# LM2587_12v.net
KiCad netlist of a schematic drawn in Altium Designer
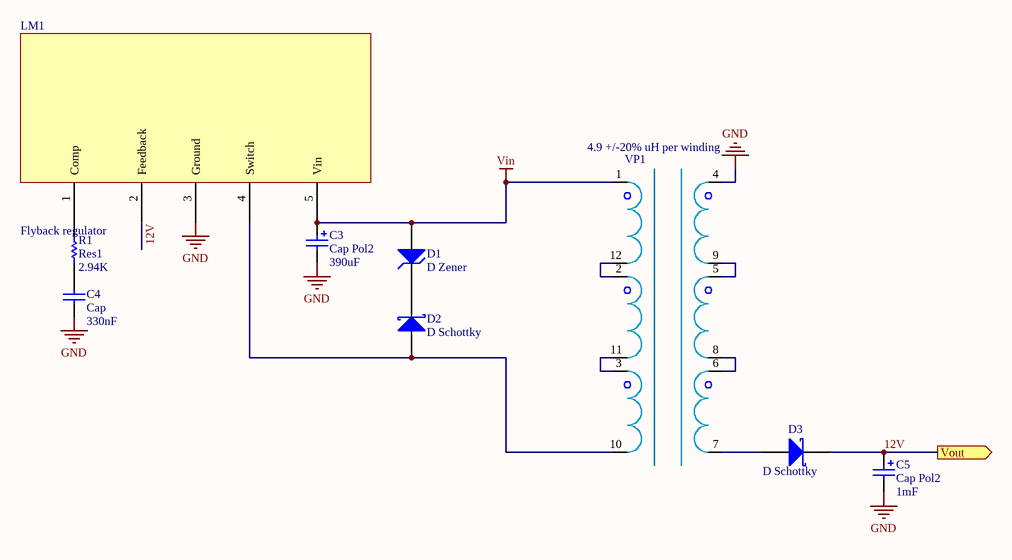
[diagram p0: LM2587_12v.SchDoc]

(export (version "E")
  (design (tool "Eeschema 10.0.6"))
  (components
    (comp (ref "C3")
      (value "Cap Pol2")
      (footprint "AXIAL-0.3")
      (description "Polarized Capacitor (Axial)")
      (fields (field (name "ALTIUM_VALUE") "390uF") (field (name "PUBLISHER") "Altium Limited"))
      (libsource (lib "Miscellaneous Devices") (part "Cap Pol2"))
    )
    (comp (ref "C4")
      (value "Cap")
      (footprint "AXIAL-0.3")
      (description "Capacitor")
      (fields (field (name "ALTIUM_VALUE") "330nF") (field (name "PUBLISHER") "Altium Limited"))
      (libsource (lib "Miscellaneous Devices") (part "Cap"))
    )
    (comp (ref "C5")
      (value "Cap Pol2")
      (footprint "AXIAL-0.3")
      (description "Polarized Capacitor (Axial)")
      (fields (field (name "ALTIUM_VALUE") "1mF") (field (name "PUBLISHER") "Altium Limited"))
      (libsource (lib "Miscellaneous Devices") (part "Cap Pol2"))
    )
    (comp (ref "D1")
      (value "D Zener")
      (footprint "DIODE")
      (description "Zener Diode")
      (fields (field (name "PUBLISHER") "Altium Limited"))
      (libsource (lib "Miscellaneous Devices") (part "D Zener"))
    )
    (comp (ref "D2")
      (value "D Schottky")
      (footprint "DIODE")
      (description "Schottky Diode")
      (fields (field (name "PUBLISHER") "Altium Limited"))
      (libsource (lib "Miscellaneous Devices") (part "D Schottky"))
    )
    (comp (ref "D3")
      (value "D Schottky")
      (footprint "DIODE")
      (description "Schottky Diode")
      (fields (field (name "PUBLISHER") "Altium Limited"))
      (libsource (lib "Miscellaneous Devices") (part "D Schottky"))
    )
    (comp (ref "LM1")
      (value "Flyback regulator")
      (footprint "TS5B")
      (libsource (lib "investigator_regulator") (part "LM2587"))
    )
    (comp (ref "R1")
      (value "Res1")
      (footprint "AXIAL-0.3")
      (description "Resistor")
      (fields (field (name "ALTIUM_VALUE") "2.94K") (field (name "PUBLISHER") "Altium Limited"))
      (libsource (lib "Miscellaneous Devices") (part "Res1"))
    )
    (comp (ref "VP1")
      (value "4.9 +/-20% uH per winding")
      (footprint "TRANSFORMER_SOP12")
      (libsource (lib "investigator_regulator") (part "VP4-0060-R"))
    )
  )
  (nets
    (net (code "1") (name "/12V") (class "Default")
      (node (ref "C5") (pin "1") (pinfunction "1_1") (pintype "passive"))
      (node (ref "D3") (pin "2") (pinfunction "K_2") (pintype "passive"))
      (node (ref "LM1") (pin "2") (pinfunction "Feedback_2") (pintype "passive"))
    )
    (net (code "2") (name "GND") (class "Default")
      (node (ref "C3") (pin "2") (pinfunction "2_2") (pintype "passive"))
      (node (ref "C4") (pin "1") (pinfunction "1_1") (pintype "passive"))
      (node (ref "C5") (pin "2") (pinfunction "2_2") (pintype "passive"))
      (node (ref "LM1") (pin "3") (pinfunction "Ground_3") (pintype "passive"))
      (node (ref "VP1") (pin "4") (pinfunction "4_4") (pintype "passive"))
    )
    (net (code "3") (name "Net-(C4-Pad2)") (class "Default")
      (node (ref "C4") (pin "2") (pinfunction "2_2") (pintype "passive"))
      (node (ref "R1") (pin "1") (pinfunction "1_1") (pintype "passive"))
    )
    (net (code "4") (name "Net-(D1-K)") (class "Default")
      (node (ref "D1") (pin "2") (pinfunction "K_2") (pintype "passive"))
      (node (ref "D2") (pin "2") (pinfunction "K_2") (pintype "passive"))
    )
    (net (code "5") (name "Net-(D2-A)") (class "Default")
      (node (ref "D2") (pin "1") (pinfunction "A_1") (pintype "passive"))
      (node (ref "LM1") (pin "4") (pinfunction "Switch_4") (pintype "passive"))
      (node (ref "VP1") (pin "10") (pinfunction "10_10") (pintype "passive"))
    )
    (net (code "6") (name "Net-(D3-A)") (class "Default")
      (node (ref "D3") (pin "1") (pinfunction "A_1") (pintype "passive"))
      (node (ref "VP1") (pin "7") (pinfunction "7_7") (pintype "passive"))
    )
    (net (code "7") (name "Net-(LM1-Comp)") (class "Default")
      (node (ref "LM1") (pin "1") (pinfunction "Comp_1") (pintype "passive"))
      (node (ref "R1") (pin "2") (pinfunction "2_2") (pintype "passive"))
    )
    (net (code "8") (name "Net-(VP1-Pad5)") (class "Default")
      (node (ref "VP1") (pin "5") (pinfunction "5_5") (pintype "passive"))
      (node (ref "VP1") (pin "9") (pinfunction "9_9") (pintype "passive"))
    )
    (net (code "9") (name "Net-(VP1-Pad6)") (class "Default")
      (node (ref "VP1") (pin "6") (pinfunction "6_6") (pintype "passive"))
      (node (ref "VP1") (pin "8") (pinfunction "8_8") (pintype "passive"))
    )
    (net (code "10") (name "Net-(VP1-Pad11)") (class "Default")
      (node (ref "VP1") (pin "11") (pinfunction "11_11") (pintype "passive"))
      (node (ref "VP1") (pin "3") (pinfunction "3_3") (pintype "passive"))
    )
    (net (code "11") (name "Net-(VP1-Pad12)") (class "Default")
      (node (ref "VP1") (pin "12") (pinfunction "12_12") (pintype "passive"))
      (node (ref "VP1") (pin "2") (pinfunction "2_2") (pintype "passive"))
    )
    (net (code "12") (name "Vin") (class "Default")
      (node (ref "C3") (pin "1") (pinfunction "1_1") (pintype "passive"))
      (node (ref "D1") (pin "1") (pinfunction "A_1") (pintype "passive"))
      (node (ref "LM1") (pin "5") (pinfunction "Vin_5") (pintype "passive"))
      (node (ref "VP1") (pin "1") (pinfunction "1_1") (pintype "passive"))
    )
  )
)
